# GPS_radiologger_v24_L70_CMWX_MAX_auto.net
KiCad netlist of a schematic drawn in EAGLE
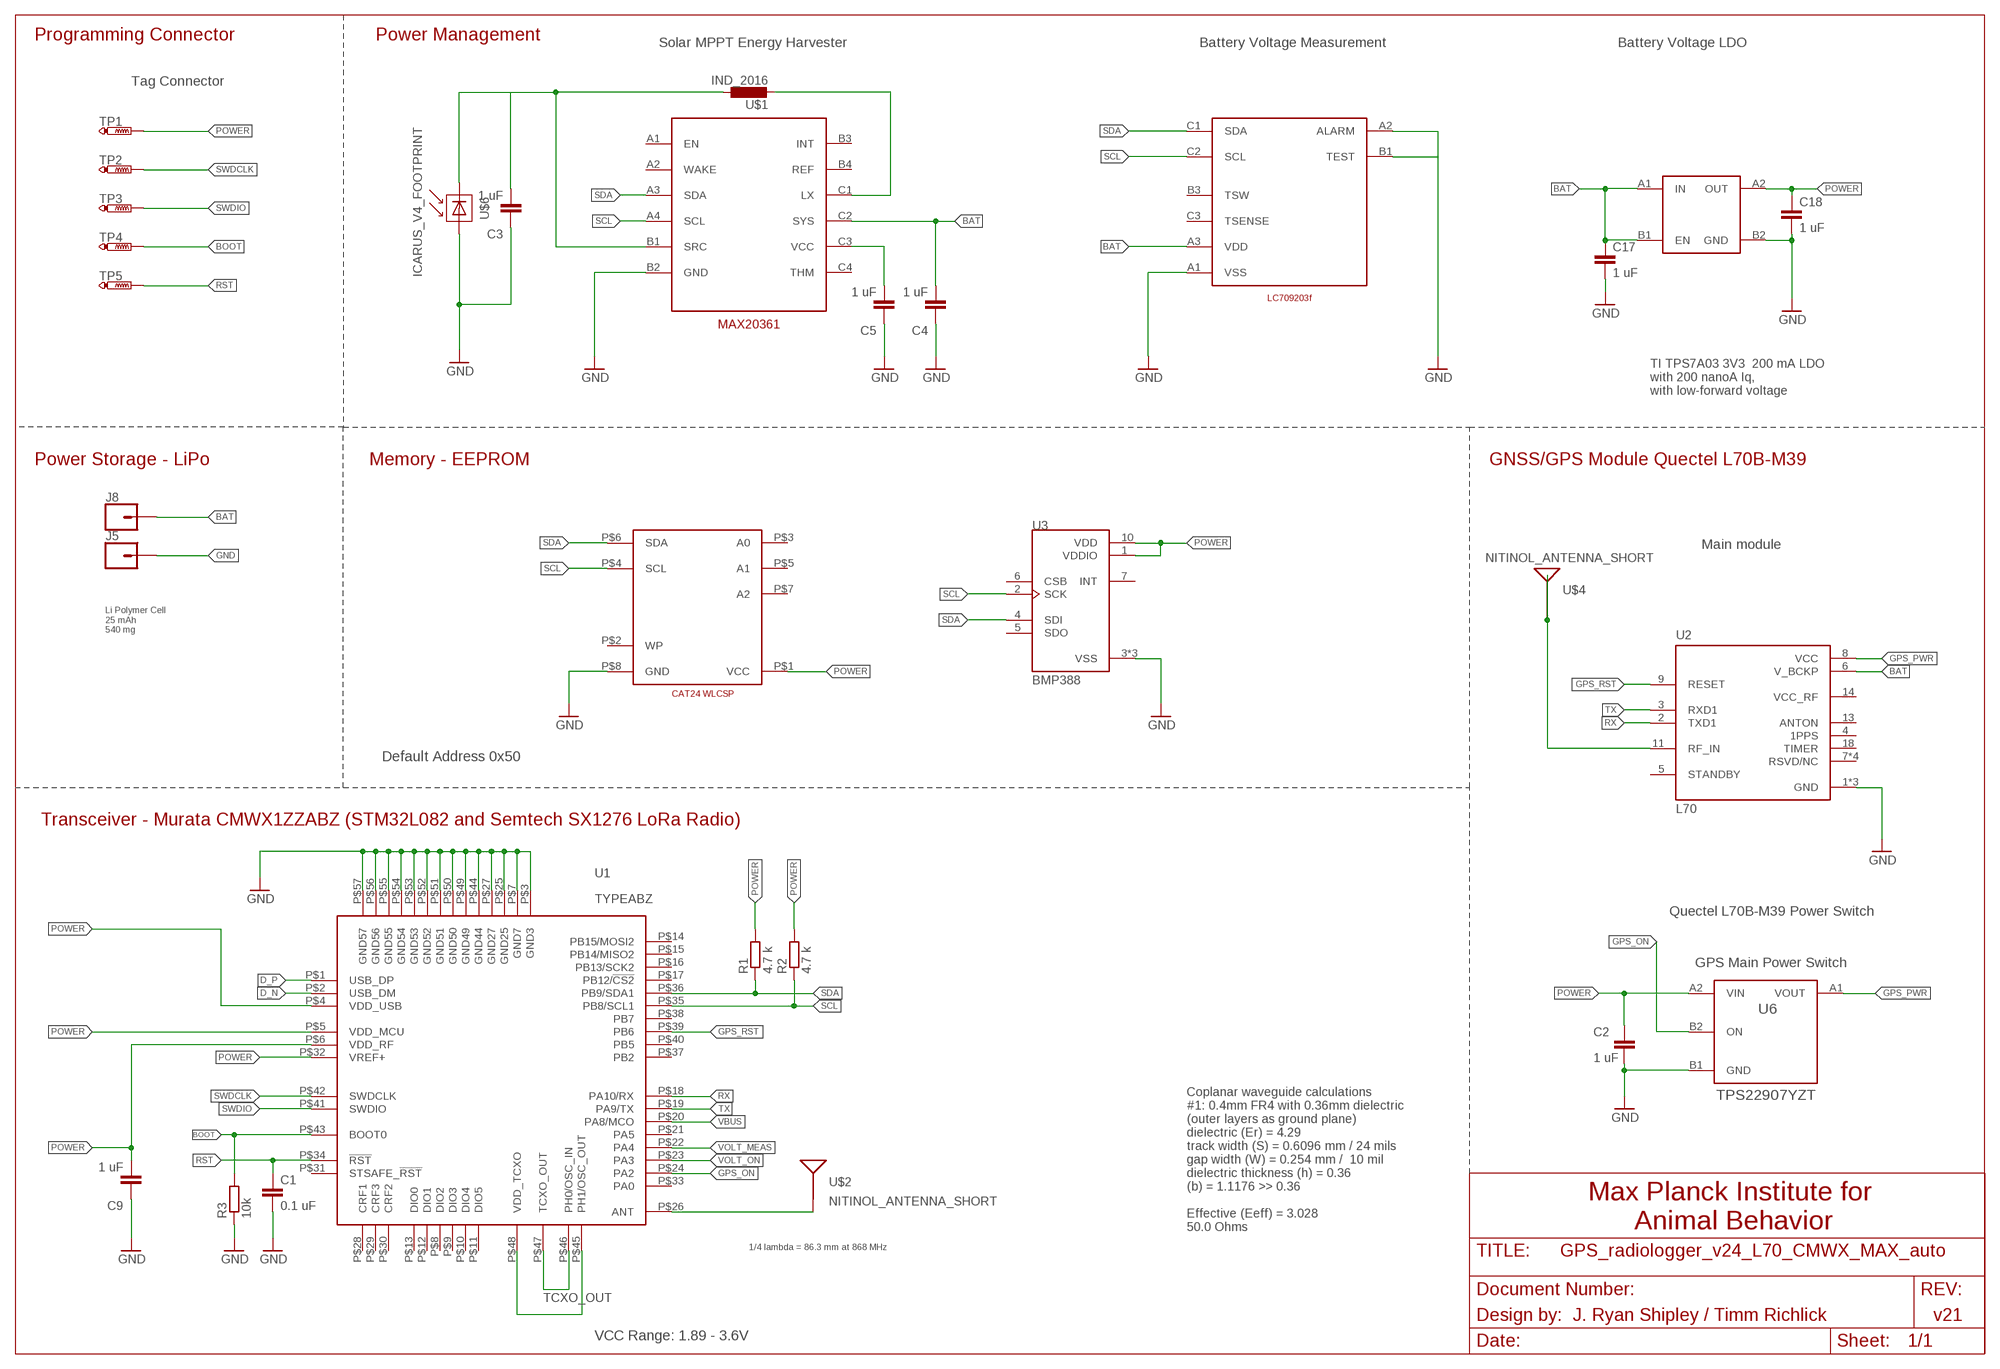
[diagram p0: schematic, sheet 1]

(export (version "E")
  (design (tool "Eeschema 10.0.6"))
  (components
    (comp (ref "C1")
      (value "0.1 uF")
      (footprint "eagle-import:C0201")
      (libsource (lib "eagle-import") (part "C-EUC0201"))
    )
    (comp (ref "C2")
      (value "1 uF")
      (footprint "eagle-import:C0201")
      (libsource (lib "eagle-import") (part "C-EUC0201"))
    )
    (comp (ref "C3")
      (value "1 uF")
      (footprint "eagle-import:C0201")
      (libsource (lib "eagle-import") (part "C-EUC0201"))
    )
    (comp (ref "C4")
      (value "1 uF")
      (footprint "eagle-import:C0201")
      (libsource (lib "eagle-import") (part "C-EUC0201"))
    )
    (comp (ref "C5")
      (value "1 uF")
      (footprint "eagle-import:C0201")
      (libsource (lib "eagle-import") (part "C-EUC0201"))
    )
    (comp (ref "C9")
      (value "1 uF")
      (footprint "eagle-import:C0201")
      (libsource (lib "eagle-import") (part "C-EUC0201"))
    )
    (comp (ref "C17")
      (value "1 uF")
      (footprint "eagle-import:0402-CAP")
      (libsource (lib "eagle-import") (part "0402CAP.KW"))
    )
    (comp (ref "C18")
      (value "1 uF")
      (footprint "eagle-import:0402-CAP")
      (libsource (lib "eagle-import") (part "0402CAP.KW"))
    )
    (comp (ref "J5")
      (value "CONN_01PTH_NO_SILK_SMALL")
      (footprint "eagle-import:1X01_SMALL")
      (libsource (lib "eagle-import") (part "CONN_01PTH_NO_SILK_SMALL"))
    )
    (comp (ref "J8")
      (value "CONN_01PTH_NO_SILK_SMALL")
      (footprint "eagle-import:1X01_SMALL")
      (libsource (lib "eagle-import") (part "CONN_01PTH_NO_SILK_SMALL"))
    )
    (comp (ref "R1")
      (value "4.7 k")
      (footprint "eagle-import:R0201")
      (libsource (lib "eagle-import") (part "R-EU_R0201"))
    )
    (comp (ref "R2")
      (value "4.7 k")
      (footprint "eagle-import:R0201")
      (libsource (lib "eagle-import") (part "R-EU_R0201"))
    )
    (comp (ref "R3")
      (value "10k")
      (footprint "eagle-import:R0201")
      (libsource (lib "eagle-import") (part "R-EU_R0201"))
    )
    (comp (ref "TP1")
      (value "PTR1TP08SQ")
      (footprint "eagle-import:TP08SQ")
      (libsource (lib "eagle-import") (part "PTR1TP08SQ"))
    )
    (comp (ref "TP2")
      (value "PTR1TP08SQ")
      (footprint "eagle-import:TP08SQ")
      (libsource (lib "eagle-import") (part "PTR1TP08SQ"))
    )
    (comp (ref "TP3")
      (value "PTR1TP08SQ")
      (footprint "eagle-import:TP08SQ")
      (libsource (lib "eagle-import") (part "PTR1TP08SQ"))
    )
    (comp (ref "TP4")
      (value "PTR1TP08SQ")
      (footprint "eagle-import:TP08SQ")
      (libsource (lib "eagle-import") (part "PTR1TP08SQ"))
    )
    (comp (ref "TP5")
      (value "PTR1TP08SQ")
      (footprint "eagle-import:TP08SQ")
      (libsource (lib "eagle-import") (part "PTR1TP08SQ"))
    )
    (comp (ref "U$1")
      (value "IND_2016")
      (footprint "eagle-import:INDC2016X120L")
      (libsource (lib "eagle-import") (part "IND_2016"))
    )
    (comp (ref "U$2")
      (value "NITINOL_ANTENNA_SHORT")
      (footprint "eagle-import:ICARUS_NITINOL_ANTENNA_SHORT")
      (libsource (lib "eagle-import") (part "NITINOL_ANTENNA_SHORT"))
    )
    (comp (ref "U$3")
      (value "TPS7A03-DSBGA")
      (footprint "eagle-import:BGA4N35P2X2_70X70X40N")
      (libsource (lib "eagle-import") (part "TPS7A03-DSBGA"))
    )
    (comp (ref "U$4")
      (value "NITINOL_ANTENNA_SHORT")
      (footprint "eagle-import:ICARUS_NITINOL_ANTENNA_SHORT")
      (libsource (lib "eagle-import") (part "NITINOL_ANTENNA_SHORT"))
    )
    (comp (ref "U$6")
      (value "ICARUS_V4_FOOTPRINT")
      (footprint "eagle-import:ICARUS_FULL_FOOTPRINT")
      (libsource (lib "eagle-import") (part "ICARUS_V4_FOOTPRINT"))
    )
    (comp (ref "U$7")
      (value "LC709203F")
      (footprint "eagle-import:BGA9N50P3X3_160X175X50N")
      (libsource (lib "eagle-import") (part "LC709203F"))
    )
    (comp (ref "U$8")
      (value "MAX20361")
      (footprint "eagle-import:BGA12N40P4X3_123X163X64N")
      (libsource (lib "eagle-import") (part "MAX20361"))
    )
    (comp (ref "U$9")
      (value "CAT24_WLCSP8")
      (footprint "eagle-import:WLCSP8")
      (libsource (lib "eagle-import") (part "CAT24_WLCSP8"))
    )
    (comp (ref "U1")
      (value "TYPEABZ")
      (footprint "eagle-import:TYPEABZ")
      (libsource (lib "eagle-import") (part "TYPEABZ"))
    )
    (comp (ref "U2")
      (value "L70")
      (footprint "eagle-import:XCVR_L70")
      (fields (field (name "MF") "Quectel"))
      (libsource (lib "eagle-import") (part "L70"))
    )
    (comp (ref "U3")
      (value "BMP388")
      (footprint "eagle-import:PQFN50P200X200X80-10N")
      (fields (field (name "MF") "Bosch Sensortec"))
      (libsource (lib "eagle-import") (part "BMP388"))
    )
    (comp (ref "U6")
      (value "TPS22907YZT")
      (footprint "eagle-import:YFP0004-DSBGA")
      (libsource (lib "eagle-import") (part "TPS22907YZT"))
    )
  )
  (nets
    (net (code "1") (name "/TCXO_OUT") (class "Default")
      (node (ref "U1") (pin "P$46") (pinfunction "PH0/OSC_IN_P$46") (pintype "bidirectional"))
      (node (ref "U1") (pin "P$47") (pinfunction "TCXO_OUT_P$47") (pintype "bidirectional"))
    )
    (net (code "2") (name "BAT") (class "Default")
      (node (ref "C17") (pin "1") (pinfunction "1_1") (pintype "passive"))
      (node (ref "C4") (pin "2") (pinfunction "2_2") (pintype "passive"))
      (node (ref "J8") (pin "P$1") (pinfunction "1_P$1") (pintype "passive"))
      (node (ref "U$3") (pin "A1") (pinfunction "IN_A1") (pintype "bidirectional"))
      (node (ref "U$3") (pin "B1") (pinfunction "EN_B1") (pintype "bidirectional"))
      (node (ref "U$7") (pin "A3") (pinfunction "VDD_A3") (pintype "bidirectional"))
      (node (ref "U$8") (pin "C2") (pinfunction "SYS_C2") (pintype "bidirectional"))
      (node (ref "U2") (pin "6") (pinfunction "V_BCKP_6") (pintype "power_in"))
    )
    (net (code "3") (name "BOOT") (class "Default")
      (node (ref "R3") (pin "2") (pinfunction "2_2") (pintype "passive"))
      (node (ref "TP4") (pin "TP") (pinfunction "TP_TP") (pintype "input"))
      (node (ref "U1") (pin "P$43") (pinfunction "BOOT0_P$43") (pintype "bidirectional"))
    )
    (net (code "4") (name "D_N") (class "Default")
      (node (ref "U1") (pin "P$2") (pinfunction "USB_DM_P$2") (pintype "bidirectional"))
    )
    (net (code "5") (name "D_P") (class "Default")
      (node (ref "U1") (pin "P$1") (pinfunction "USB_DP_P$1") (pintype "bidirectional"))
    )
    (net (code "6") (name "GND") (class "Default")
      (node (ref "C1") (pin "2") (pinfunction "2_2") (pintype "passive"))
      (node (ref "C17") (pin "2") (pinfunction "2_2") (pintype "passive"))
      (node (ref "C18") (pin "2") (pinfunction "2_2") (pintype "passive"))
      (node (ref "C2") (pin "2") (pinfunction "2_2") (pintype "passive"))
      (node (ref "C3") (pin "1") (pinfunction "1_1") (pintype "passive"))
      (node (ref "C4") (pin "1") (pinfunction "1_1") (pintype "passive"))
      (node (ref "C5") (pin "1") (pinfunction "1_1") (pintype "passive"))
      (node (ref "C9") (pin "1") (pinfunction "1_1") (pintype "passive"))
      (node (ref "J5") (pin "P$1") (pinfunction "1_P$1") (pintype "passive"))
      (node (ref "R3") (pin "1") (pinfunction "1_1") (pintype "passive"))
      (node (ref "U$3") (pin "B2") (pinfunction "GND_B2") (pintype "bidirectional"))
      (node (ref "U$6") (pin "P$2") (pinfunction "MINUS_P$2") (pintype "passive"))
      (node (ref "U$7") (pin "A1") (pinfunction "VSS_A1") (pintype "bidirectional"))
      (node (ref "U$7") (pin "A2") (pinfunction "ALARM_A2") (pintype "bidirectional"))
      (node (ref "U$7") (pin "B1") (pinfunction "TEST_B1") (pintype "bidirectional"))
      (node (ref "U$8") (pin "B2") (pinfunction "GND_B2") (pintype "bidirectional"))
      (node (ref "U$9") (pin "P$8") (pinfunction "GND_P$8") (pintype "bidirectional"))
      (node (ref "U1") (pin "P$25") (pinfunction "GND25_P$25") (pintype "power_in"))
      (node (ref "U1") (pin "P$27") (pinfunction "GND27_P$27") (pintype "power_in"))
      (node (ref "U1") (pin "P$3") (pinfunction "GND3_P$3") (pintype "power_in"))
      (node (ref "U1") (pin "P$44") (pinfunction "GND44_P$44") (pintype "power_in"))
      (node (ref "U1") (pin "P$49") (pinfunction "GND49_P$49") (pintype "power_in"))
      (node (ref "U1") (pin "P$50") (pinfunction "GND50_P$50") (pintype "power_in"))
      (node (ref "U1") (pin "P$51") (pinfunction "GND51_P$51") (pintype "power_in"))
      (node (ref "U1") (pin "P$52") (pinfunction "GND52_P$52") (pintype "power_in"))
      (node (ref "U1") (pin "P$53") (pinfunction "GND53_P$53") (pintype "power_in"))
      (node (ref "U1") (pin "P$54") (pinfunction "GND54_P$54") (pintype "power_in"))
      (node (ref "U1") (pin "P$55") (pinfunction "GND55_P$55") (pintype "power_in"))
      (node (ref "U1") (pin "P$56") (pinfunction "GND56_P$56") (pintype "power_in"))
      (node (ref "U1") (pin "P$57") (pinfunction "GND57_P$57") (pintype "power_in"))
      (node (ref "U1") (pin "P$7") (pinfunction "GND7_P$7") (pintype "power_in"))
      (node (ref "U2") (pin "1") (pinfunction "GND_1") (pintype "power_in"))
      (node (ref "U2") (pin "10") (pinfunction "GND_10") (pintype "power_in"))
      (node (ref "U2") (pin "12") (pinfunction "GND_12") (pintype "power_in"))
      (node (ref "U3") (pin "3") (pinfunction "VSS_3") (pintype "power_in"))
      (node (ref "U3") (pin "8") (pinfunction "VSS_8") (pintype "power_in"))
      (node (ref "U3") (pin "9") (pinfunction "VSS_9") (pintype "power_in"))
      (node (ref "U6") (pin "B1") (pinfunction "GND_B1") (pintype "bidirectional"))
    )
    (net (code "7") (name "GPS_ON") (class "Default")
      (node (ref "U1") (pin "P$24") (pinfunction "PA2_P$24") (pintype "bidirectional"))
      (node (ref "U6") (pin "B2") (pinfunction "ON_B2") (pintype "bidirectional"))
    )
    (net (code "8") (name "GPS_PWR") (class "Default")
      (node (ref "U2") (pin "8") (pinfunction "VCC_8") (pintype "power_in"))
      (node (ref "U6") (pin "A1") (pinfunction "VOUT_A1") (pintype "bidirectional"))
    )
    (net (code "9") (name "GPS_RST") (class "Default")
      (node (ref "U1") (pin "P$39") (pinfunction "PB6_P$39") (pintype "bidirectional"))
      (node (ref "U2") (pin "9") (pinfunction "RESET_9") (pintype "input"))
    )
    (net (code "10") (name "Net-(U$6-PLUS)") (class "Default")
      (node (ref "C3") (pin "2") (pinfunction "2_2") (pintype "passive"))
      (node (ref "U$1") (pin "1") (pinfunction "1_1") (pintype "passive"))
      (node (ref "U$6") (pin "P$1") (pinfunction "PLUS_P$1") (pintype "passive"))
      (node (ref "U$8") (pin "B1") (pinfunction "SRC_B1") (pintype "bidirectional"))
    )
    (net (code "11") (name "Net-(U$8-LX)") (class "Default")
      (node (ref "U$1") (pin "2") (pinfunction "2_2") (pintype "passive"))
      (node (ref "U$8") (pin "C1") (pinfunction "LX_C1") (pintype "bidirectional"))
    )
    (net (code "12") (name "Net-(U$8-VCC)") (class "Default")
      (node (ref "C5") (pin "2") (pinfunction "2_2") (pintype "passive"))
      (node (ref "U$8") (pin "C3") (pinfunction "VCC_C3") (pintype "bidirectional"))
    )
    (net (code "13") (name "Net-(U1-ANT)") (class "Default")
      (node (ref "U$2") (pin "1") (pinfunction "SIGNAL_1") (pintype "bidirectional"))
      (node (ref "U$2") (pin "2") (pinfunction "SIGNAL_2") (pintype "bidirectional"))
      (node (ref "U$2") (pin "3") (pinfunction "SIGNAL_3") (pintype "bidirectional"))
      (node (ref "U1") (pin "P$26") (pinfunction "ANT_P$26") (pintype "bidirectional"))
    )
    (net (code "14") (name "Net-(U1-PH1{slash}OSC_OUT)") (class "Default")
      (node (ref "U1") (pin "P$45") (pinfunction "PH1/OSC_OUT_P$45") (pintype "bidirectional"))
      (node (ref "U1") (pin "P$48") (pinfunction "VDD_TCXO_P$48") (pintype "power_in"))
    )
    (net (code "15") (name "Net-(U2-RF_IN)") (class "Default")
      (node (ref "U$4") (pin "1") (pinfunction "SIGNAL_1") (pintype "bidirectional"))
      (node (ref "U$4") (pin "2") (pinfunction "SIGNAL_2") (pintype "bidirectional"))
      (node (ref "U$4") (pin "3") (pinfunction "SIGNAL_3") (pintype "bidirectional"))
      (node (ref "U2") (pin "11") (pinfunction "RF_IN_11") (pintype "input"))
    )
    (net (code "16") (name "POWER") (class "Default")
      (node (ref "C18") (pin "1") (pinfunction "1_1") (pintype "passive"))
      (node (ref "C2") (pin "1") (pinfunction "1_1") (pintype "passive"))
      (node (ref "C9") (pin "2") (pinfunction "2_2") (pintype "passive"))
      (node (ref "R1") (pin "2") (pinfunction "2_2") (pintype "passive"))
      (node (ref "R2") (pin "2") (pinfunction "2_2") (pintype "passive"))
      (node (ref "TP1") (pin "TP") (pinfunction "TP_TP") (pintype "input"))
      (node (ref "U$3") (pin "A2") (pinfunction "OUT_A2") (pintype "bidirectional"))
      (node (ref "U$9") (pin "P$1") (pinfunction "VCC_P$1") (pintype "bidirectional"))
      (node (ref "U1") (pin "P$32") (pinfunction "VREF+_P$32") (pintype "power_in"))
      (node (ref "U1") (pin "P$4") (pinfunction "VDD_USB_P$4") (pintype "power_in"))
      (node (ref "U1") (pin "P$5") (pinfunction "VDD_MCU_P$5") (pintype "power_in"))
      (node (ref "U1") (pin "P$6") (pinfunction "VDD_RF_P$6") (pintype "power_in"))
      (node (ref "U3") (pin "1") (pinfunction "VDDIO_1") (pintype "power_in"))
      (node (ref "U3") (pin "10") (pinfunction "VDD_10") (pintype "power_in"))
      (node (ref "U6") (pin "A2") (pinfunction "VIN_A2") (pintype "bidirectional"))
    )
    (net (code "17") (name "RST") (class "Default")
      (node (ref "C1") (pin "1") (pinfunction "1_1") (pintype "passive"))
      (node (ref "TP5") (pin "TP") (pinfunction "TP_TP") (pintype "input"))
      (node (ref "U1") (pin "P$34") (pinfunction "~{RST}_P$34") (pintype "bidirectional"))
    )
    (net (code "18") (name "RX") (class "Default")
      (node (ref "U1") (pin "P$18") (pinfunction "PA10/RX_P$18") (pintype "bidirectional"))
      (node (ref "U2") (pin "2") (pinfunction "TXD1_2") (pintype "output"))
    )
    (net (code "19") (name "SCL") (class "Default")
      (node (ref "R2") (pin "1") (pinfunction "1_1") (pintype "passive"))
      (node (ref "U$7") (pin "C2") (pinfunction "SCL_C2") (pintype "bidirectional"))
      (node (ref "U$8") (pin "A4") (pinfunction "SCL_A4") (pintype "bidirectional"))
      (node (ref "U$9") (pin "P$4") (pinfunction "SCL_P$4") (pintype "bidirectional"))
      (node (ref "U1") (pin "P$35") (pinfunction "PB8/SCL1_P$35") (pintype "bidirectional"))
      (node (ref "U3") (pin "2") (pinfunction "SCK_2") (pintype "input"))
    )
    (net (code "20") (name "SDA") (class "Default")
      (node (ref "R1") (pin "1") (pinfunction "1_1") (pintype "passive"))
      (node (ref "U$7") (pin "C1") (pinfunction "SDA_C1") (pintype "bidirectional"))
      (node (ref "U$8") (pin "A3") (pinfunction "SDA_A3") (pintype "bidirectional"))
      (node (ref "U$9") (pin "P$6") (pinfunction "SDA_P$6") (pintype "bidirectional"))
      (node (ref "U1") (pin "P$36") (pinfunction "PB9/SDA1_P$36") (pintype "bidirectional"))
      (node (ref "U3") (pin "4") (pinfunction "SDI_4") (pintype "bidirectional"))
    )
    (net (code "21") (name "SWDCLK") (class "Default")
      (node (ref "TP2") (pin "TP") (pinfunction "TP_TP") (pintype "input"))
      (node (ref "U1") (pin "P$42") (pinfunction "SWDCLK_P$42") (pintype "bidirectional"))
    )
    (net (code "22") (name "SWDIO") (class "Default")
      (node (ref "TP3") (pin "TP") (pinfunction "TP_TP") (pintype "input"))
      (node (ref "U1") (pin "P$41") (pinfunction "SWDIO_P$41") (pintype "bidirectional"))
    )
    (net (code "23") (name "TX") (class "Default")
      (node (ref "U1") (pin "P$19") (pinfunction "PA9/TX_P$19") (pintype "bidirectional"))
      (node (ref "U2") (pin "3") (pinfunction "RXD1_3") (pintype "input"))
    )
    (net (code "24") (name "VBUS") (class "Default")
      (node (ref "U1") (pin "P$20") (pinfunction "PA8/MCO_P$20") (pintype "bidirectional"))
    )
    (net (code "25") (name "VOLT_MEAS") (class "Default")
      (node (ref "U1") (pin "P$22") (pinfunction "PA4_P$22") (pintype "bidirectional"))
    )
    (net (code "26") (name "VOLT_ON") (class "Default")
      (node (ref "U1") (pin "P$23") (pinfunction "PA3_P$23") (pintype "bidirectional"))
    )
    (net (code "27") (name "unconnected-(U$7-TSENSE-PadC3)") (class "Default")
      (node (ref "U$7") (pin "C3") (pinfunction "TSENSE_C3") (pintype "bidirectional"))
    )
    (net (code "28") (name "unconnected-(U$7-TSW-PadB3)") (class "Default")
      (node (ref "U$7") (pin "B3") (pinfunction "TSW_B3") (pintype "bidirectional"))
    )
    (net (code "29") (name "unconnected-(U$8-EN-PadA1)") (class "Default")
      (node (ref "U$8") (pin "A1") (pinfunction "EN_A1") (pintype "bidirectional"))
    )
    (net (code "30") (name "unconnected-(U$8-INT-PadB3)") (class "Default")
      (node (ref "U$8") (pin "B3") (pinfunction "INT_B3") (pintype "bidirectional"))
    )
    (net (code "31") (name "unconnected-(U$8-REF-PadB4)") (class "Default")
      (node (ref "U$8") (pin "B4") (pinfunction "REF_B4") (pintype "bidirectional"))
    )
    (net (code "32") (name "unconnected-(U$8-THM-PadC4)") (class "Default")
      (node (ref "U$8") (pin "C4") (pinfunction "THM_C4") (pintype "bidirectional"))
    )
    (net (code "33") (name "unconnected-(U$8-WAKE-PadA2)") (class "Default")
      (node (ref "U$8") (pin "A2") (pinfunction "WAKE_A2") (pintype "bidirectional"))
    )
    (net (code "34") (name "unconnected-(U$9-A0-PadP$3)") (class "Default")
      (node (ref "U$9") (pin "P$3") (pinfunction "A0_P$3") (pintype "bidirectional"))
    )
    (net (code "35") (name "unconnected-(U$9-A1-PadP$5)") (class "Default")
      (node (ref "U$9") (pin "P$5") (pinfunction "A1_P$5") (pintype "bidirectional"))
    )
    (net (code "36") (name "unconnected-(U$9-A2-PadP$7)") (class "Default")
      (node (ref "U$9") (pin "P$7") (pinfunction "A2_P$7") (pintype "bidirectional"))
    )
    (net (code "37") (name "unconnected-(U$9-WP-PadP$2)") (class "Default")
      (node (ref "U$9") (pin "P$2") (pinfunction "WP_P$2") (pintype "bidirectional"))
    )
    (net (code "38") (name "unconnected-(U1-CRF1-PadP$28)") (class "Default")
      (node (ref "U1") (pin "P$28") (pinfunction "CRF1_P$28") (pintype "no_connect"))
    )
    (net (code "39") (name "unconnected-(U1-CRF2-PadP$30)") (class "Default")
      (node (ref "U1") (pin "P$30") (pinfunction "CRF2_P$30") (pintype "no_connect"))
    )
    (net (code "40") (name "unconnected-(U1-CRF3-PadP$29)") (class "Default")
      (node (ref "U1") (pin "P$29") (pinfunction "CRF3_P$29") (pintype "no_connect"))
    )
    (net (code "41") (name "unconnected-(U1-DIO0-PadP$13)") (class "Default")
      (node (ref "U1") (pin "P$13") (pinfunction "DIO0_P$13") (pintype "no_connect"))
    )
    (net (code "42") (name "unconnected-(U1-DIO1-PadP$12)") (class "Default")
      (node (ref "U1") (pin "P$12") (pinfunction "DIO1_P$12") (pintype "no_connect"))
    )
    (net (code "43") (name "unconnected-(U1-DIO2-PadP$8)") (class "Default")
      (node (ref "U1") (pin "P$8") (pinfunction "DIO2_P$8") (pintype "no_connect"))
    )
    (net (code "44") (name "unconnected-(U1-DIO3-PadP$9)") (class "Default")
      (node (ref "U1") (pin "P$9") (pinfunction "DIO3_P$9") (pintype "no_connect"))
    )
    (net (code "45") (name "unconnected-(U1-DIO4-PadP$10)") (class "Default")
      (node (ref "U1") (pin "P$10") (pinfunction "DIO4_P$10") (pintype "bidirectional"))
    )
    (net (code "46") (name "unconnected-(U1-DIO5-PadP$11)") (class "Default")
      (node (ref "U1") (pin "P$11") (pinfunction "DIO5_P$11") (pintype "bidirectional"))
    )
    (net (code "47") (name "unconnected-(U1-PA0-PadP$33)") (class "Default")
      (node (ref "U1") (pin "P$33") (pinfunction "PA0_P$33") (pintype "bidirectional"))
    )
    (net (code "48") (name "unconnected-(U1-PA5-PadP$21)") (class "Default")
      (node (ref "U1") (pin "P$21") (pinfunction "PA5_P$21") (pintype "bidirectional"))
    )
    (net (code "49") (name "unconnected-(U1-PB2-PadP$37)") (class "Default")
      (node (ref "U1") (pin "P$37") (pinfunction "PB2_P$37") (pintype "bidirectional"))
    )
    (net (code "50") (name "unconnected-(U1-PB5-PadP$40)") (class "Default")
      (node (ref "U1") (pin "P$40") (pinfunction "PB5_P$40") (pintype "bidirectional"))
    )
    (net (code "51") (name "unconnected-(U1-PB7-PadP$38)") (class "Default")
      (node (ref "U1") (pin "P$38") (pinfunction "PB7_P$38") (pintype "bidirectional"))
    )
    (net (code "52") (name "unconnected-(U1-PB12{slash}~{CS2}-PadP$17)") (class "Default")
      (node (ref "U1") (pin "P$17") (pinfunction "PB12/~{CS2}_P$17") (pintype "bidirectional"))
    )
    (net (code "53") (name "unconnected-(U1-PB13{slash}SCK2-PadP$16)") (class "Default")
      (node (ref "U1") (pin "P$16") (pinfunction "PB13/SCK2_P$16") (pintype "bidirectional"))
    )
    (net (code "54") (name "unconnected-(U1-PB14{slash}MISO2-PadP$15)") (class "Default")
      (node (ref "U1") (pin "P$15") (pinfunction "PB14/MISO2_P$15") (pintype "bidirectional"))
    )
    (net (code "55") (name "unconnected-(U1-PB15{slash}MOSI2-PadP$14)") (class "Default")
      (node (ref "U1") (pin "P$14") (pinfunction "PB15/MOSI2_P$14") (pintype "bidirectional"))
    )
    (net (code "56") (name "unconnected-(U1-STSAFE_~{RST}-PadP$31)") (class "Default")
      (node (ref "U1") (pin "P$31") (pinfunction "STSAFE_~{RST}_P$31") (pintype "bidirectional"))
    )
    (net (code "57") (name "unconnected-(U2-1PPS-Pad4)") (class "Default")
      (node (ref "U2") (pin "4") (pinfunction "1PPS_4") (pintype "output"))
    )
    (net (code "58") (name "unconnected-(U2-ANTON-Pad13)") (class "Default")
      (node (ref "U2") (pin "13") (pinfunction "ANTON_13") (pintype "output"))
    )
    (net (code "59") (name "unconnected-(U2-RSVD{slash}NC-Pad7)") (class "Default")
      (node (ref "U2") (pin "7") (pinfunction "RSVD/NC_7") (pintype "no_connect"))
    )
    (net (code "60") (name "unconnected-(U2-RSVD{slash}NC-Pad15)") (class "Default")
      (node (ref "U2") (pin "15") (pinfunction "RSVD/NC_15") (pintype "no_connect"))
    )
    (net (code "61") (name "unconnected-(U2-RSVD{slash}NC-Pad16)") (class "Default")
      (node (ref "U2") (pin "16") (pinfunction "RSVD/NC_16") (pintype "no_connect"))
    )
    (net (code "62") (name "unconnected-(U2-RSVD{slash}NC-Pad17)") (class "Default")
      (node (ref "U2") (pin "17") (pinfunction "RSVD/NC_17") (pintype "no_connect"))
    )
    (net (code "63") (name "unconnected-(U2-STANDBY-Pad5)") (class "Default")
      (node (ref "U2") (pin "5") (pinfunction "STANDBY_5") (pintype "input"))
    )
    (net (code "64") (name "unconnected-(U2-TIMER-Pad18)") (class "Default")
      (node (ref "U2") (pin "18") (pinfunction "TIMER_18") (pintype "output"))
    )
    (net (code "65") (name "unconnected-(U2-VCC_RF-Pad14)") (class "Default")
      (node (ref "U2") (pin "14") (pinfunction "VCC_RF_14") (pintype "output"))
    )
    (net (code "66") (name "unconnected-(U3-CSB-Pad6)") (class "Default")
      (node (ref "U3") (pin "6") (pinfunction "CSB_6") (pintype "input"))
    )
    (net (code "67") (name "unconnected-(U3-INT-Pad7)") (class "Default")
      (node (ref "U3") (pin "7") (pinfunction "INT_7") (pintype "output"))
    )
    (net (code "68") (name "unconnected-(U3-SDO-Pad5)") (class "Default")
      (node (ref "U3") (pin "5") (pinfunction "SDO_5") (pintype "bidirectional"))
    )
  )
)
